# Poactuator_Connectors.net
KiCad netlist of a schematic drawn in Altium Designer
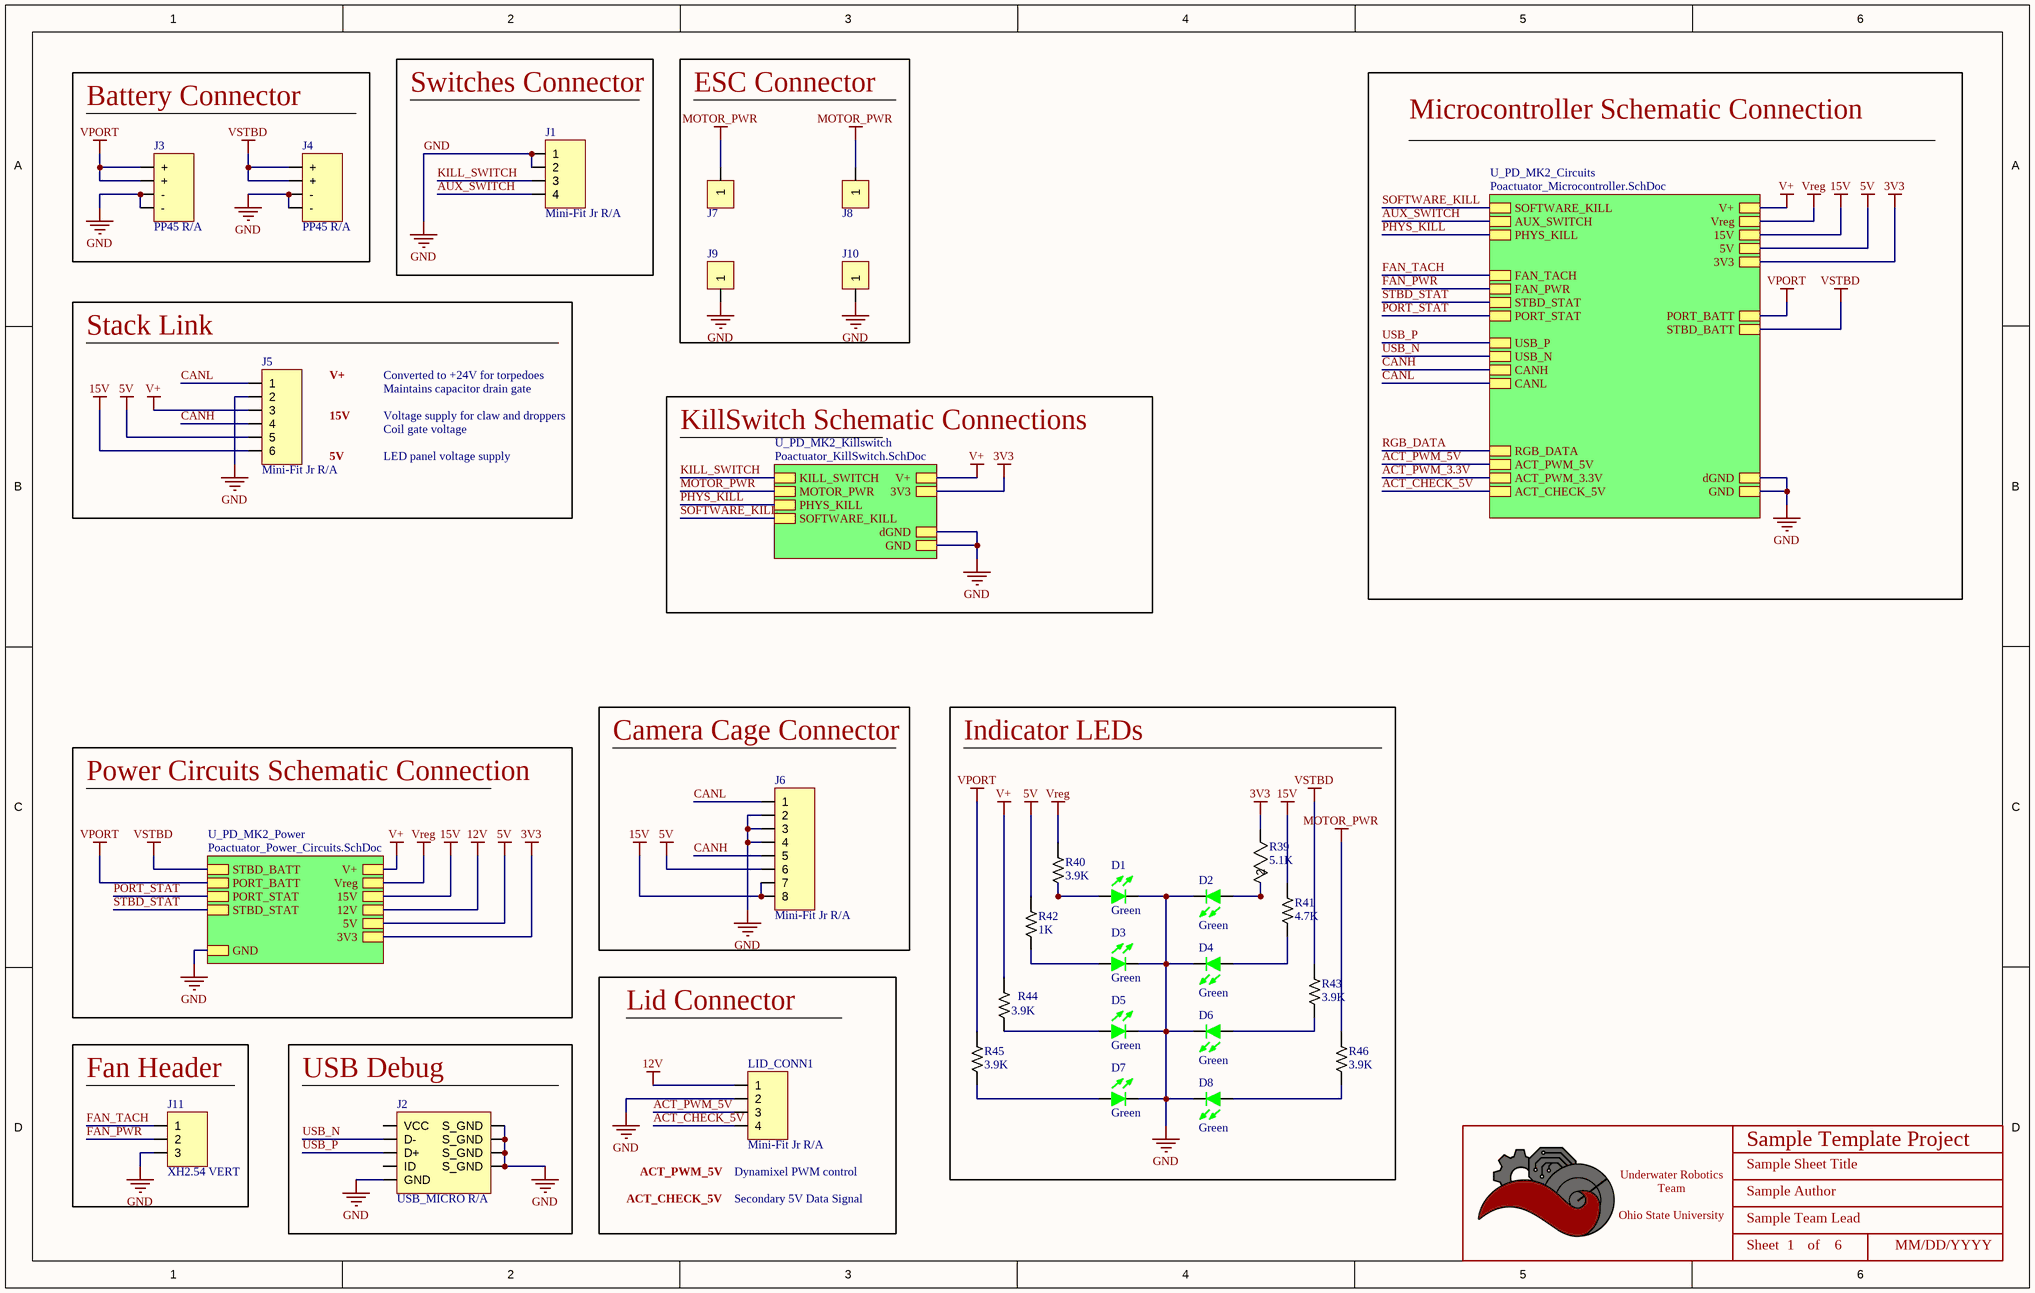
[diagram p0: Poactuator_Connectors.SchDoc]

(export (version "E")
  (design (tool "Eeschema 10.0.6"))
  (components
    (comp (ref "D1")
      (value "IN-S63AT5G")
      (footprint "LED_0603")
      (description "LED Green Vf= 3V If = 0.005A\r\nIN-S63AT5G")
      (fields (field (name "COLOR") "Green") (field (name "MADE BY") "Robert Pafford"))
      (libsource (lib "Diodes") (part "LED_Green_0603_3V"))
    )
    (comp (ref "D2")
      (value "IN-S63AT5G")
      (footprint "LED_0603")
      (description "LED Green Vf= 3V If = 0.005A\r\nIN-S63AT5G")
      (fields (field (name "COLOR") "Green") (field (name "MADE BY") "Robert Pafford"))
      (libsource (lib "Diodes") (part "LED_Green_0603_3V"))
    )
    (comp (ref "D3")
      (value "IN-S63AT5G")
      (footprint "LED_0603")
      (description "LED Green Vf= 3V If = 0.005A\r\nIN-S63AT5G")
      (fields (field (name "COLOR") "Green") (field (name "MADE BY") "Robert Pafford"))
      (libsource (lib "Diodes") (part "LED_Green_0603_3V"))
    )
    (comp (ref "D4")
      (value "IN-S63AT5G")
      (footprint "LED_0603")
      (description "LED Green Vf= 3V If = 0.005A\r\nIN-S63AT5G")
      (fields (field (name "COLOR") "Green") (field (name "MADE BY") "Robert Pafford"))
      (libsource (lib "Diodes") (part "LED_Green_0603_3V"))
    )
    (comp (ref "D5")
      (value "IN-S63AT5G")
      (footprint "LED_0603")
      (description "LED Green Vf= 3V If = 0.005A\r\nIN-S63AT5G")
      (fields (field (name "COLOR") "Green") (field (name "MADE BY") "Robert Pafford"))
      (libsource (lib "Diodes") (part "LED_Green_0603_3V"))
    )
    (comp (ref "D6")
      (value "IN-S63AT5G")
      (footprint "LED_0603")
      (description "LED Green Vf= 3V If = 0.005A\r\nIN-S63AT5G")
      (fields (field (name "COLOR") "Green") (field (name "MADE BY") "Robert Pafford"))
      (libsource (lib "Diodes") (part "LED_Green_0603_3V"))
    )
    (comp (ref "D7")
      (value "IN-S63AT5G")
      (footprint "LED_0603")
      (description "LED Green Vf= 3V If = 0.005A\r\nIN-S63AT5G")
      (fields (field (name "COLOR") "Green") (field (name "MADE BY") "Robert Pafford"))
      (libsource (lib "Diodes") (part "LED_Green_0603_3V"))
    )
    (comp (ref "D8")
      (value "IN-S63AT5G")
      (footprint "LED_0603")
      (description "LED Green Vf= 3V If = 0.005A\r\nIN-S63AT5G")
      (fields (field (name "COLOR") "Green") (field (name "MADE BY") "Robert Pafford"))
      (libsource (lib "Diodes") (part "LED_Green_0603_3V"))
    )
    (comp (ref "J1")
      (value "Mini-Fit Jr R/A")
      (footprint "CONN_MOLEX_MINIFIT JR_4 POS_R/A")
      (description "Molex Minifit Jr. 5569 \r\n4 Pos R/A Natural")
      (fields (field (name "MANUFACTURER") "Molex") (field (name "CREATED BY") "Flip B"))
      (libsource (lib "Connectors") (part "CONN_MOLEX_MINIFIT JR_4POS_R/A"))
    )
    (comp (ref "J2")
      (value "USB_MICRO R/A")
      (footprint "CONN_MINIUSB")
      (description "Amphenol Micro USB-B\r\nUSB2.0 5 Pin Right Angle SMD")
      (fields (field (name "MANUFACTURER") "Amphenol") (field (name "CREATED BY") "Flip B"))
      (libsource (lib "Connectors") (part "CONN_MICROUSB"))
    )
    (comp (ref "J3")
      (value "PP45 R/A")
      (footprint "CONN_ANDERSON_PP45_4 POS_R/A")
      (description "Anderson PP45\r\n4 Pos R/A Red/Black")
      (fields (field (name "MANUFACTURER") "Anderson") (field (name "CREATED BY") "Flip B"))
      (libsource (lib "Connectors") (part "CONN_ANDERSON_2x2_R/A"))
    )
    (comp (ref "J4")
      (value "PP45 R/A")
      (footprint "CONN_ANDERSON_PP45_4 POS_R/A")
      (description "Anderson PP45\r\n4 Pos R/A Red/Black")
      (fields (field (name "MANUFACTURER") "Anderson") (field (name "CREATED BY") "Flip B"))
      (libsource (lib "Connectors") (part "CONN_ANDERSON_2x2_R/A"))
    )
    (comp (ref "J5")
      (value "Mini-Fit Jr R/A")
      (footprint "CONN_MOLEX_MINIFIT JR_6 POS_R/A")
      (description "Molex Minifit Jr. 5569 \r\n6 Pos R/A Natural")
      (fields (field (name "MANUFACTURER") "Molex") (field (name "CREATED BY") "Flip B"))
      (libsource (lib "Connectors") (part "CONN_MOLEX_MINIFIT JR_6POS_R/A"))
    )
    (comp (ref "J6")
      (value "Mini-Fit Jr R/A")
      (footprint "CONN_MOLEX_MINIFIT JR_8 POS_R/A")
      (description "Molex Minifit Jr. 5569 \r\n8 Pos R/A Natural")
      (fields (field (name "MANUFACTURER") "Molex") (field (name "CREATED BY") "Flip B"))
      (libsource (lib "Connectors") (part "CONN_MOLEX_MINIFIT JR_8POS_R/A"))
    )
    (comp (ref "J7")
      (value "Redcube M4 Term 85A")
      (footprint "Redcube M4 Term 85A")
      (fields (field (name "CREATED BY") "Nahtan Ayer"))
      (libsource (lib "Connectors") (part "Redcube M4 Term 85A"))
    )
    (comp (ref "J8")
      (value "Redcube M4 Term 85A")
      (footprint "Redcube M4 Term 85A")
      (fields (field (name "CREATED BY") "Nahtan Ayer"))
      (libsource (lib "Connectors") (part "Redcube M4 Term 85A"))
    )
    (comp (ref "J9")
      (value "Redcube M4 Term 85A")
      (footprint "Redcube M4 Term 85A")
      (fields (field (name "CREATED BY") "Nahtan Ayer"))
      (libsource (lib "") (part "Redcube M4 Term 85A_1"))
    )
    (comp (ref "J10")
      (value "Redcube M4 Term 85A")
      (footprint "Redcube M4 Term 85A")
      (fields (field (name "CREATED BY") "Nahtan Ayer"))
      (libsource (lib "") (part "Redcube M4 Term 85A_1"))
    )
    (comp (ref "J11")
      (value "XH2.54 VERT")
      (footprint "CONN_JST_XH254_3POS_VERT")
      (description "JST XH 2.54mm Pitch 3 Pos Vertical")
      (fields (field (name "MANUFACTURER") "JST") (field (name "CREATED BY") "Robert P"))
      (libsource (lib "Connectors") (part "CONN_JST_XH254_3POS_VERT"))
    )
    (comp (ref "LID_CONN1")
      (value "Mini-Fit Jr R/A")
      (footprint "CONN_MOLEX_MINIFIT JR_4 POS_R/A")
      (description "Molex Minifit Jr. 5569 \r\n4 Pos R/A Natural")
      (fields (field (name "MANUFACTURER") "Molex") (field (name "CREATED BY") "Flip B"))
      (libsource (lib "Connectors") (part "CONN_MOLEX_MINIFIT JR_4POS_R/A"))
    )
    (comp (ref "R39")
      (value "5.1K")
      (footprint "RC0603N_PAN")
      (description "5.1 kOhms ±0.1% 0.1W, 1/10W Chip Resistor 0603 (1608 Metric) Automotive AEC-Q200 Thin Film")
      (fields
        (field (name "MANUFACTURER_PART_NUMBER") "ERA-3AEB512V")
        (field (name "COPYRIGHT") "Copyright (C) 2023 Ultra Librarian. All rights reserved.")
      )
      (libsource (lib "Resistors") (part "ERA-3AEB512V_2"))
    )
    (comp (ref "R40")
      (value "3.9k Ohm 5% 1/10W")
      (footprint "RESISTOR_0603")
      (description "RES 3.9k OHM 1% 1/10W 0603")
      (fields
        (field (name "TOLERANCE") "+/- 1%")
        (field (name "VALUE  (OHMS)") "3.9K")
        (field (name "MADE BY") "Robert Pafford")
      )
      (libsource (lib "Resistors") (part "RESISTOR_3.9K_0603"))
    )
    (comp (ref "R41")
      (value "4.7k Ohm 5% 1/10W")
      (footprint "RESISTOR_0603")
      (description "RES 4.7k OHM 5% 1/10W 0603")
      (fields
        (field (name "TOLERANCE") "+/- 5%")
        (field (name "VALUE  (OHMS)") "4.7K")
        (field (name "MADE BY") "Robert Pafford")
      )
      (libsource (lib "Resistors") (part "RESISTOR_4.7K_0603"))
    )
    (comp (ref "R42")
      (value "1k Ohm 5% 1/8W")
      (footprint "RESISTOR_0603")
      (description "RES 1k OHM 5% 1/8W 0603")
      (fields
        (field (name "TOLERANCE") "+/- 5%")
        (field (name "VALUE  (OHMS)") "1K")
        (field (name "MADE BY") "Robert Pafford")
      )
      (libsource (lib "Resistors") (part "RESISTOR_1K_0603"))
    )
    (comp (ref "R43")
      (value "3.9k Ohm 5% 1/10W")
      (footprint "RESISTOR_0603")
      (description "RES 3.9k OHM 1% 1/10W 0603")
      (fields
        (field (name "TOLERANCE") "+/- 1%")
        (field (name "VALUE  (OHMS)") "3.9K")
        (field (name "MADE BY") "Robert Pafford")
      )
      (libsource (lib "Resistors") (part "RESISTOR_3.9K_0603"))
    )
    (comp (ref "R44")
      (value "3.9k Ohm 5% 1/10W")
      (footprint "RESISTOR_0603")
      (description "RES 3.9k OHM 1% 1/10W 0603")
      (fields
        (field (name "TOLERANCE") "+/- 1%")
        (field (name "VALUE  (OHMS)") "3.9K")
        (field (name "MADE BY") "Robert Pafford")
      )
      (libsource (lib "Resistors") (part "RESISTOR_3.9K_0603"))
    )
    (comp (ref "R45")
      (value "3.9k Ohm 5% 1/10W")
      (footprint "RESISTOR_0603")
      (description "RES 3.9k OHM 1% 1/10W 0603")
      (fields
        (field (name "TOLERANCE") "+/- 1%")
        (field (name "VALUE  (OHMS)") "3.9K")
        (field (name "MADE BY") "Robert Pafford")
      )
      (libsource (lib "Resistors") (part "RESISTOR_3.9K_0603"))
    )
    (comp (ref "R46")
      (value "3.9k Ohm 5% 1/10W")
      (footprint "RESISTOR_0603")
      (description "RES 3.9k OHM 1% 1/10W 0603")
      (fields
        (field (name "TOLERANCE") "+/- 1%")
        (field (name "VALUE  (OHMS)") "3.9K")
        (field (name "MADE BY") "Robert Pafford")
      )
      (libsource (lib "Resistors") (part "RESISTOR_3.9K_0603"))
    )
  )
  (nets
    (net (code "1") (name "/ACT_CHECK_5V") (class "Default")
      (node (ref "LID_CONN1") (pin "4") (pinfunction "4_4") (pintype "passive"))
    )
    (net (code "3") (name "/ACT_PWM_5V") (class "Default")
      (node (ref "LID_CONN1") (pin "3") (pinfunction "3_3") (pintype "passive"))
    )
    (net (code "4") (name "/AUX_SWITCH") (class "Default")
      (node (ref "J1") (pin "4") (pinfunction "4_4") (pintype "passive"))
    )
    (net (code "5") (name "/CANH") (class "Default")
      (node (ref "J5") (pin "4") (pinfunction "4_4") (pintype "passive"))
      (node (ref "J6") (pin "5") (pinfunction "5_5") (pintype "passive"))
    )
    (net (code "6") (name "/CANL") (class "Default")
      (node (ref "J5") (pin "1") (pinfunction "1_1") (pintype "passive"))
      (node (ref "J6") (pin "1") (pinfunction "1_1") (pintype "passive"))
    )
    (net (code "7") (name "/FAN_PWR") (class "Default")
      (node (ref "J11") (pin "2") (pinfunction "2_2") (pintype "passive"))
    )
    (net (code "8") (name "/FAN_TACH") (class "Default")
      (node (ref "J11") (pin "1") (pinfunction "1_1") (pintype "passive"))
    )
    (net (code "9") (name "/KILL_SWITCH") (class "Default")
      (node (ref "J1") (pin "3") (pinfunction "3_3") (pintype "passive"))
    )
    (net (code "15") (name "/USB_N") (class "Default")
      (node (ref "J2") (pin "2") (pinfunction "D-_2") (pintype "passive"))
    )
    (net (code "16") (name "/USB_P") (class "Default")
      (node (ref "J2") (pin "3") (pinfunction "D+_3") (pintype "passive"))
    )
    (net (code "17") (name "3V3") (class "Default")
      (node (ref "R39") (pin "1") (pinfunction "1_1") (pintype "passive"))
    )
    (net (code "18") (name "5V") (class "Default")
      (node (ref "J5") (pin "5") (pinfunction "5_5") (pintype "passive"))
      (node (ref "J6") (pin "6") (pinfunction "6_6") (pintype "passive"))
      (node (ref "R42") (pin "1") (pinfunction "1_1") (pintype "passive"))
    )
    (net (code "19") (name "12V") (class "Default")
      (node (ref "LID_CONN1") (pin "1") (pinfunction "1_1") (pintype "passive"))
    )
    (net (code "20") (name "15V") (class "Default")
      (node (ref "J5") (pin "6") (pinfunction "6_6") (pintype "passive"))
      (node (ref "J6") (pin "7") (pinfunction "7_7") (pintype "passive"))
      (node (ref "J6") (pin "8") (pinfunction "8_8") (pintype "passive"))
      (node (ref "R41") (pin "1") (pinfunction "1_1") (pintype "passive"))
    )
    (net (code "21") (name "GND") (class "Default")
      (node (ref "D1") (pin "2") (pinfunction "2_2") (pintype "passive"))
      (node (ref "D2") (pin "2") (pinfunction "2_2") (pintype "passive"))
      (node (ref "D3") (pin "2") (pinfunction "2_2") (pintype "passive"))
      (node (ref "D4") (pin "2") (pinfunction "2_2") (pintype "passive"))
      (node (ref "D5") (pin "2") (pinfunction "2_2") (pintype "passive"))
      (node (ref "D6") (pin "2") (pinfunction "2_2") (pintype "passive"))
      (node (ref "D7") (pin "2") (pinfunction "2_2") (pintype "passive"))
      (node (ref "D8") (pin "2") (pinfunction "2_2") (pintype "passive"))
      (node (ref "J1") (pin "1") (pinfunction "1_1") (pintype "passive"))
      (node (ref "J1") (pin "2") (pinfunction "2_2") (pintype "passive"))
      (node (ref "J10") (pin "1") (pinfunction "1_1") (pintype "passive"))
      (node (ref "J11") (pin "3") (pinfunction "3_3") (pintype "passive"))
      (node (ref "J2") (pin "5") (pinfunction "GND_5") (pintype "passive"))
      (node (ref "J2") (pin "6") (pinfunction "S_GND_6") (pintype "passive"))
      (node (ref "J2") (pin "7") (pinfunction "S_GND_7") (pintype "passive"))
      (node (ref "J2") (pin "8") (pinfunction "S_GND_8") (pintype "passive"))
      (node (ref "J2") (pin "9") (pinfunction "S_GND_9") (pintype "passive"))
      (node (ref "J3") (pin "3") (pinfunction "-_3") (pintype "passive"))
      (node (ref "J3") (pin "4") (pinfunction "-_4") (pintype "passive"))
      (node (ref "J4") (pin "3") (pinfunction "-_3") (pintype "passive"))
      (node (ref "J4") (pin "4") (pinfunction "-_4") (pintype "passive"))
      (node (ref "J5") (pin "2") (pinfunction "2_2") (pintype "passive"))
      (node (ref "J6") (pin "2") (pinfunction "2_2") (pintype "passive"))
      (node (ref "J6") (pin "3") (pinfunction "3_3") (pintype "passive"))
      (node (ref "J6") (pin "4") (pinfunction "4_4") (pintype "passive"))
      (node (ref "J9") (pin "1") (pinfunction "1_1") (pintype "passive"))
      (node (ref "LID_CONN1") (pin "2") (pinfunction "2_2") (pintype "passive"))
    )
    (net (code "22") (name "MOTOR_PWR") (class "Default")
      (node (ref "J7") (pin "1") (pinfunction "1_1") (pintype "passive"))
      (node (ref "J8") (pin "1") (pinfunction "1_1") (pintype "passive"))
      (node (ref "R46") (pin "1") (pinfunction "1_1") (pintype "passive"))
    )
    (net (code "23") (name "Net-(D1-Pad1)") (class "Default")
      (node (ref "D1") (pin "1") (pinfunction "1_1") (pintype "passive"))
      (node (ref "R40") (pin "2") (pinfunction "2_2") (pintype "passive"))
    )
    (net (code "24") (name "Net-(D2-Pad1)") (class "Default")
      (node (ref "D2") (pin "1") (pinfunction "1_1") (pintype "passive"))
      (node (ref "R39") (pin "2") (pinfunction "2_2") (pintype "passive"))
    )
    (net (code "25") (name "Net-(D3-Pad1)") (class "Default")
      (node (ref "D3") (pin "1") (pinfunction "1_1") (pintype "passive"))
      (node (ref "R42") (pin "2") (pinfunction "2_2") (pintype "passive"))
    )
    (net (code "26") (name "Net-(D4-Pad1)") (class "Default")
      (node (ref "D4") (pin "1") (pinfunction "1_1") (pintype "passive"))
      (node (ref "R41") (pin "2") (pinfunction "2_2") (pintype "passive"))
    )
    (net (code "27") (name "Net-(D5-Pad1)") (class "Default")
      (node (ref "D5") (pin "1") (pinfunction "1_1") (pintype "passive"))
      (node (ref "R44") (pin "2") (pinfunction "2_2") (pintype "passive"))
    )
    (net (code "28") (name "Net-(D6-Pad1)") (class "Default")
      (node (ref "D6") (pin "1") (pinfunction "1_1") (pintype "passive"))
      (node (ref "R43") (pin "2") (pinfunction "2_2") (pintype "passive"))
    )
    (net (code "29") (name "Net-(D7-Pad1)") (class "Default")
      (node (ref "D7") (pin "1") (pinfunction "1_1") (pintype "passive"))
      (node (ref "R45") (pin "2") (pinfunction "2_2") (pintype "passive"))
    )
    (net (code "30") (name "Net-(D8-Pad1)") (class "Default")
      (node (ref "D8") (pin "1") (pinfunction "1_1") (pintype "passive"))
      (node (ref "R46") (pin "2") (pinfunction "2_2") (pintype "passive"))
    )
    (net (code "31") (name "V+") (class "Default")
      (node (ref "J5") (pin "3") (pinfunction "3_3") (pintype "passive"))
      (node (ref "R44") (pin "1") (pinfunction "1_1") (pintype "passive"))
    )
    (net (code "32") (name "VPORT") (class "Default")
      (node (ref "J3") (pin "1") (pinfunction "+_1") (pintype "passive"))
      (node (ref "J3") (pin "2") (pinfunction "+_2") (pintype "passive"))
      (node (ref "R45") (pin "1") (pinfunction "1_1") (pintype "passive"))
    )
    (net (code "33") (name "VSTBD") (class "Default")
      (node (ref "J4") (pin "1") (pinfunction "+_1") (pintype "passive"))
      (node (ref "J4") (pin "2") (pinfunction "+_2") (pintype "passive"))
      (node (ref "R43") (pin "1") (pinfunction "1_1") (pintype "passive"))
    )
    (net (code "34") (name "Vreg") (class "Default")
      (node (ref "R40") (pin "1") (pinfunction "1_1") (pintype "passive"))
    )
    (net (code "35") (name "unconnected-(J2-ID-Pad4)") (class "Default")
      (node (ref "J2") (pin "4") (pinfunction "ID_4") (pintype "passive"))
    )
    (net (code "36") (name "unconnected-(J2-VCC-Pad1)") (class "Default")
      (node (ref "J2") (pin "1") (pinfunction "VCC_1") (pintype "passive"))
    )
  )
)
